# Sheet1.net
KiCad netlist of a schematic drawn in Altium Designer
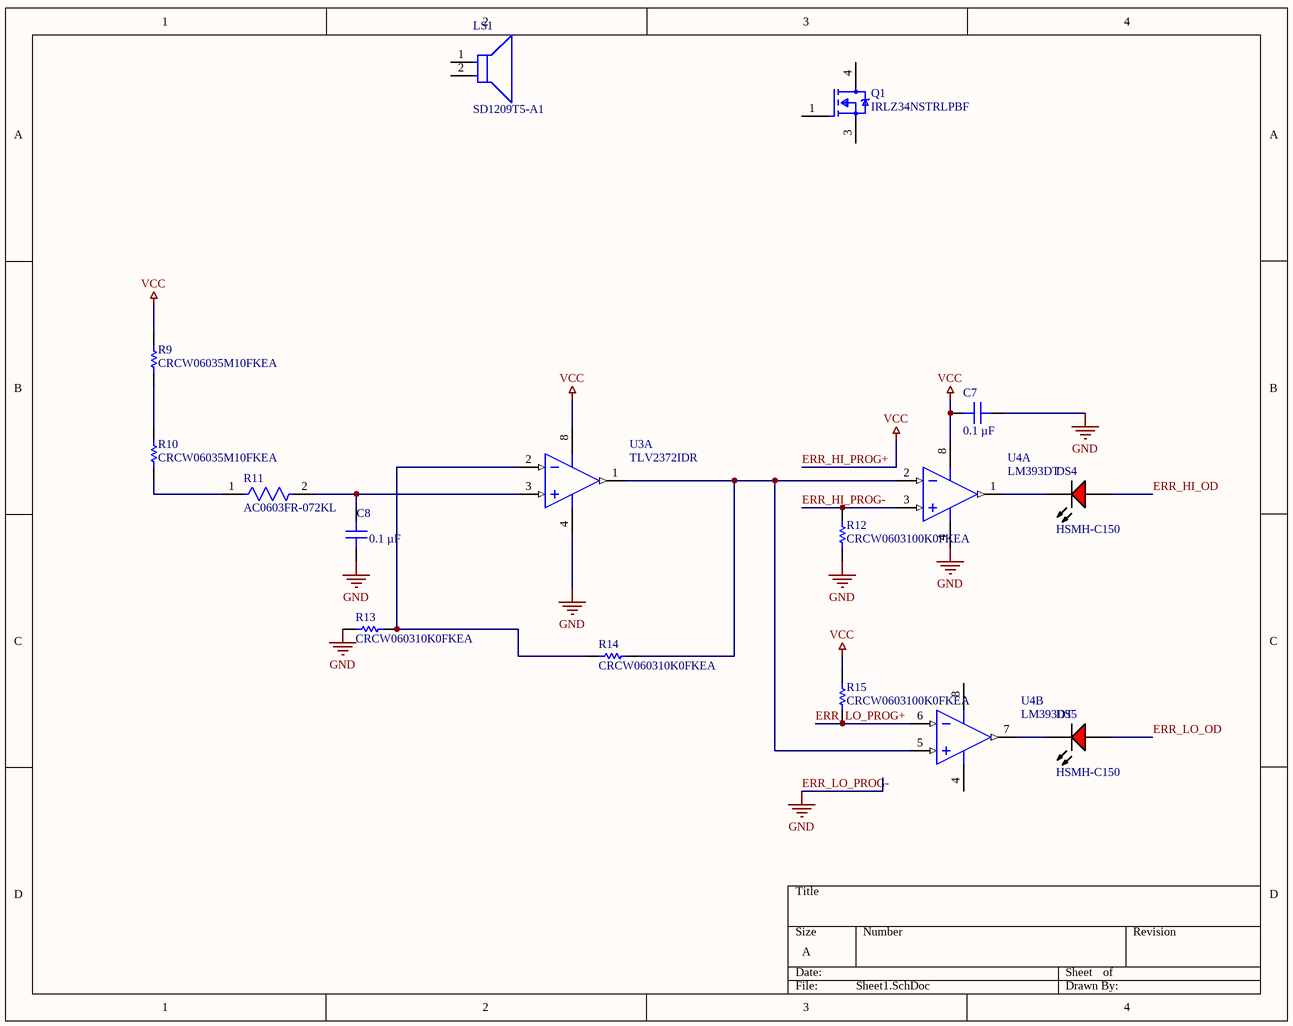
[diagram p0: Sheet1.SchDoc]

(export (version "E")
  (design (tool "Eeschema 10.0.6"))
  (components
    (comp (ref "C7")
      (value "0.1 µF")
      (footprint "CAP 0603_1608")
      (description "CAP CER 0.1UF 50V X7R 0603")
      (fields (field (name "PART NUMBER") "C0603X104J5RACAUTO") (field (name "MANUFACTURER") "KEMET"))
      (libsource (lib "Celestial Altium Library - altium_library") (part "Capacitor"))
    )
    (comp (ref "C8")
      (value "0.1 µF")
      (footprint "CAP 0603_1608")
      (description "CAP CER 0.1UF 50V X7R 0603")
      (fields (field (name "PART NUMBER") "C0603X104J5RACAUTO") (field (name "MANUFACTURER") "KEMET"))
      (libsource (lib "Celestial Altium Library - altium_library") (part "Capacitor"))
    )
    (comp (ref "DS4")
      (value "HSMH-C150")
      (footprint "AVAG-HSMX-C150_V")
      (description "LED Uni-Color Red, 65 mW, 25 mA, -40 to 85 degC, 2-Pin SMD, RoHS, Tape and Reel")
      (fields (field (name "MANUFACTURER") "Avago"))
      (libsource (lib "Altium Content Vault") (part "LED-RED-AK-2"))
    )
    (comp (ref "DS5")
      (value "HSMH-C150")
      (footprint "AVAG-HSMX-C150_V")
      (description "LED Uni-Color Red, 65 mW, 25 mA, -40 to 85 degC, 2-Pin SMD, RoHS, Tape and Reel")
      (fields (field (name "MANUFACTURER") "Avago"))
      (libsource (lib "Altium Content Vault") (part "LED-RED-AK-2"))
    )
    (comp (ref "LS1")
      (value "SD1209T5-A1")
      (footprint "FP-SD1209-MFG")
      (description "AUDIO MAGNETIC XDCR 3-6V TH")
      (libsource (lib "Altium Content Vault") (part "1973c4b650225fd2ddacaff6b763965"))
    )
    (comp (ref "Q1")
      (value "IRLZ34NSTRLPBF")
      (footprint "FP-PG-TO263-3-MFG")
      (description "MOSFET N-CH 55V 30A D2PAK")
      (libsource (lib "Altium Content Vault") (part "d7870aa5ef5e57eb3883acff98ff17f"))
    )
    (comp (ref "R9")
      (value "CRCW06035M10FKEA")
      (footprint "RESC1609X50X30NL10T20")
      (fields (field (name "MANUFACTURER") "Vishay Dale"))
      (libsource (lib "Altium Content Vault") (part "RES"))
    )
    (comp (ref "R10")
      (value "CRCW06035M10FKEA")
      (footprint "RESC1609X50X30NL10T20")
      (fields (field (name "MANUFACTURER") "Vishay Dale"))
      (libsource (lib "Altium Content Vault") (part "RES"))
    )
    (comp (ref "R11")
      (value "AC0603FR-072KL")
      (footprint "FP-AC0603-IPC_B")
      (description "RES 2kΩ 1.00% 0.1W 0603")
      (fields (field (name "TOLERANCE") "1%"))
      (libsource (lib "Altium Content Vault") (part "1029c3af85768c4190bb7ad29bc67b5"))
    )
    (comp (ref "R12")
      (value "CRCW0603100K0FKEA")
      (footprint "RESC1609X50X30NL8T20")
      (description "Chip Resistor, 100 KOhm, +/- 1%, 100 mW, -55 to 155 degC, 0603 (1608 Metric), RoHS, Tape and Reel")
      (fields (field (name "MANUFACTURER") "Vishay Semiconductor"))
      (libsource (lib "Altium Content Vault") (part "RES-2"))
    )
    (comp (ref "R13")
      (value "CRCW060310K0FKEA")
      (footprint "RESC1609X50X30NL8T20")
      (description "Chip Resistor, 10 KOhm, +/- 1%, 100 mW, -55 to 155 degC, 0603 (1608 Metric), RoHS, Tape and Reel")
      (fields (field (name "MANUFACTURER") "Vishay Semiconductor"))
      (libsource (lib "Altium Content Vault") (part "RES-2"))
    )
    (comp (ref "R14")
      (value "CRCW060310K0FKEA")
      (footprint "RESC1609X50X30NL8T20")
      (description "Chip Resistor, 10 KOhm, +/- 1%, 100 mW, -55 to 155 degC, 0603 (1608 Metric), RoHS, Tape and Reel")
      (fields (field (name "MANUFACTURER") "Vishay Semiconductor"))
      (libsource (lib "Altium Content Vault") (part "RES-2"))
    )
    (comp (ref "R15")
      (value "CRCW0603100K0FKEA")
      (footprint "RESC1609X50X30NL8T20")
      (description "Chip Resistor, 100 KOhm, +/- 1%, 100 mW, -55 to 155 degC, 0603 (1608 Metric), RoHS, Tape and Reel")
      (fields (field (name "MANUFACTURER") "Vishay Semiconductor"))
      (libsource (lib "Altium Content Vault") (part "RES-2"))
    )
    (comp (ref "U3")
      (value "TLV2372IDR")
      (footprint "D0008A_M")
      (fields (field (name "MANUFACTURER") "Texas Instruments"))
      (libsource (lib "Altium Content Vault") (part "TI-TLV_TLC-8"))
    )
    (comp (ref "U4")
      (value "LM393DT")
      (footprint "STM-SO-8_D_L")
      (description "Low-Power, Dual-Voltage Comparator, 2 to 36 V, 0 to 70 degC, 8-Pin SOIC (SO), RoHS, Tape and Reel")
      (fields (field (name "MANUFACTURER") "STMicroelectronics"))
      (libsource (lib "Altium Content Vault") (part "STM-LM393-SO8"))
    )
  )
  (nets
    (net (code "1") (name "/ERR_HI_OD") (class "Default")
      (node (ref "DS4") (pin "1") (pinfunction "A_1") (pintype "passive"))
    )
    (net (code "2") (name "/ERR_HI_PROG-") (class "Default")
      (node (ref "R12") (pin "1") (pinfunction "1_1") (pintype "passive"))
      (node (ref "U4") (pin "3") (pinfunction "IN1+_3") (pintype "input"))
    )
    (net (code "3") (name "/ERR_LO_OD") (class "Default")
      (node (ref "DS5") (pin "1") (pinfunction "A_1") (pintype "passive"))
    )
    (net (code "4") (name "/ERR_LO_PROG+") (class "Default")
      (node (ref "R15") (pin "2") (pinfunction "2_2") (pintype "passive"))
      (node (ref "U4") (pin "6") (pinfunction "IN2-_6") (pintype "input"))
    )
    (net (code "5") (name "GND") (class "Default")
      (node (ref "C7") (pin "1") (pinfunction "1_1") (pintype "passive"))
      (node (ref "C8") (pin "1") (pinfunction "1_1") (pintype "passive"))
      (node (ref "R12") (pin "2") (pinfunction "2_2") (pintype "passive"))
      (node (ref "R13") (pin "1") (pinfunction "1_1") (pintype "passive"))
      (node (ref "U3") (pin "4") (pinfunction "GND_4") (pintype "power_in"))
      (node (ref "U4") (pin "4") (pinfunction "VCC-_4") (pintype "power_in"))
    )
    (net (code "6") (name "Net-(DS4-K)") (class "Default")
      (node (ref "DS4") (pin "2") (pinfunction "K_2") (pintype "passive"))
      (node (ref "U4") (pin "1") (pinfunction "OUT1_1") (pintype "output"))
    )
    (net (code "7") (name "Net-(DS5-K)") (class "Default")
      (node (ref "DS5") (pin "2") (pinfunction "K_2") (pintype "passive"))
      (node (ref "U4") (pin "7") (pinfunction "OUT2_7") (pintype "output"))
    )
    (net (code "8") (name "Net-(R10-Pad1)") (class "Default")
      (node (ref "R10") (pin "1") (pinfunction "1_1") (pintype "passive"))
      (node (ref "R11") (pin "1") (pinfunction "1_1") (pintype "passive"))
    )
    (net (code "9") (name "Net-(R10-Pad2)") (class "Default")
      (node (ref "R10") (pin "2") (pinfunction "2_2") (pintype "passive"))
      (node (ref "R9") (pin "1") (pinfunction "1_1") (pintype "passive"))
    )
    (net (code "10") (name "Net-(U3A-IN1+)") (class "Default")
      (node (ref "C8") (pin "2") (pinfunction "2_2") (pintype "passive"))
      (node (ref "R11") (pin "2") (pinfunction "2_2") (pintype "passive"))
      (node (ref "U3") (pin "3") (pinfunction "IN1+_3") (pintype "input"))
    )
    (net (code "11") (name "Net-(U3A-IN1-)") (class "Default")
      (node (ref "R13") (pin "2") (pinfunction "2_2") (pintype "passive"))
      (node (ref "R14") (pin "1") (pinfunction "1_1") (pintype "passive"))
      (node (ref "U3") (pin "2") (pinfunction "IN1-_2") (pintype "input"))
    )
    (net (code "12") (name "Net-(U3A-OUT1)") (class "Default")
      (node (ref "R14") (pin "2") (pinfunction "2_2") (pintype "passive"))
      (node (ref "U3") (pin "1") (pinfunction "OUT1_1") (pintype "output"))
      (node (ref "U4") (pin "2") (pinfunction "IN1-_2") (pintype "input"))
      (node (ref "U4") (pin "5") (pinfunction "IN2+_5") (pintype "input"))
    )
    (net (code "13") (name "VCC") (class "Default")
      (node (ref "C7") (pin "2") (pinfunction "2_2") (pintype "passive"))
      (node (ref "R15") (pin "1") (pinfunction "1_1") (pintype "passive"))
      (node (ref "R9") (pin "2") (pinfunction "2_2") (pintype "passive"))
      (node (ref "U3") (pin "8") (pinfunction "VDD_8") (pintype "power_in"))
      (node (ref "U4") (pin "8") (pinfunction "VCC+_8") (pintype "power_in"))
    )
    (net (code "14") (name "unconnected-(LS1-A-Pad2)") (class "Default")
      (node (ref "LS1") (pin "2") (pinfunction "A_2") (pintype "passive"))
    )
    (net (code "15") (name "unconnected-(LS1-C-Pad1)") (class "Default")
      (node (ref "LS1") (pin "1") (pinfunction "C_1") (pintype "passive"))
    )
    (net (code "16") (name "unconnected-(Q1-D-Pad4)") (class "Default")
      (node (ref "Q1") (pin "4") (pinfunction "D_4") (pintype "passive"))
    )
    (net (code "17") (name "unconnected-(Q1-G-Pad1)") (class "Default")
      (node (ref "Q1") (pin "1") (pinfunction "G_1") (pintype "passive"))
    )
    (net (code "18") (name "unconnected-(Q1-S-Pad3)") (class "Default")
      (node (ref "Q1") (pin "3") (pinfunction "S_3") (pintype "passive"))
    )
    (net (code "19") (name "unconnected-(U4B-VCC+-Pad8)") (class "Default")
      (node (ref "U4") (pin "8") (pinfunction "VCC+_8") (pintype "power_in"))
    )
    (net (code "20") (name "unconnected-(U4B-VCC--Pad4)") (class "Default")
      (node (ref "U4") (pin "4") (pinfunction "VCC-_4") (pintype "power_in"))
    )
  )
)
